# ESP-MGMT.net
KiCad netlist of a schematic drawn in Altium Designer
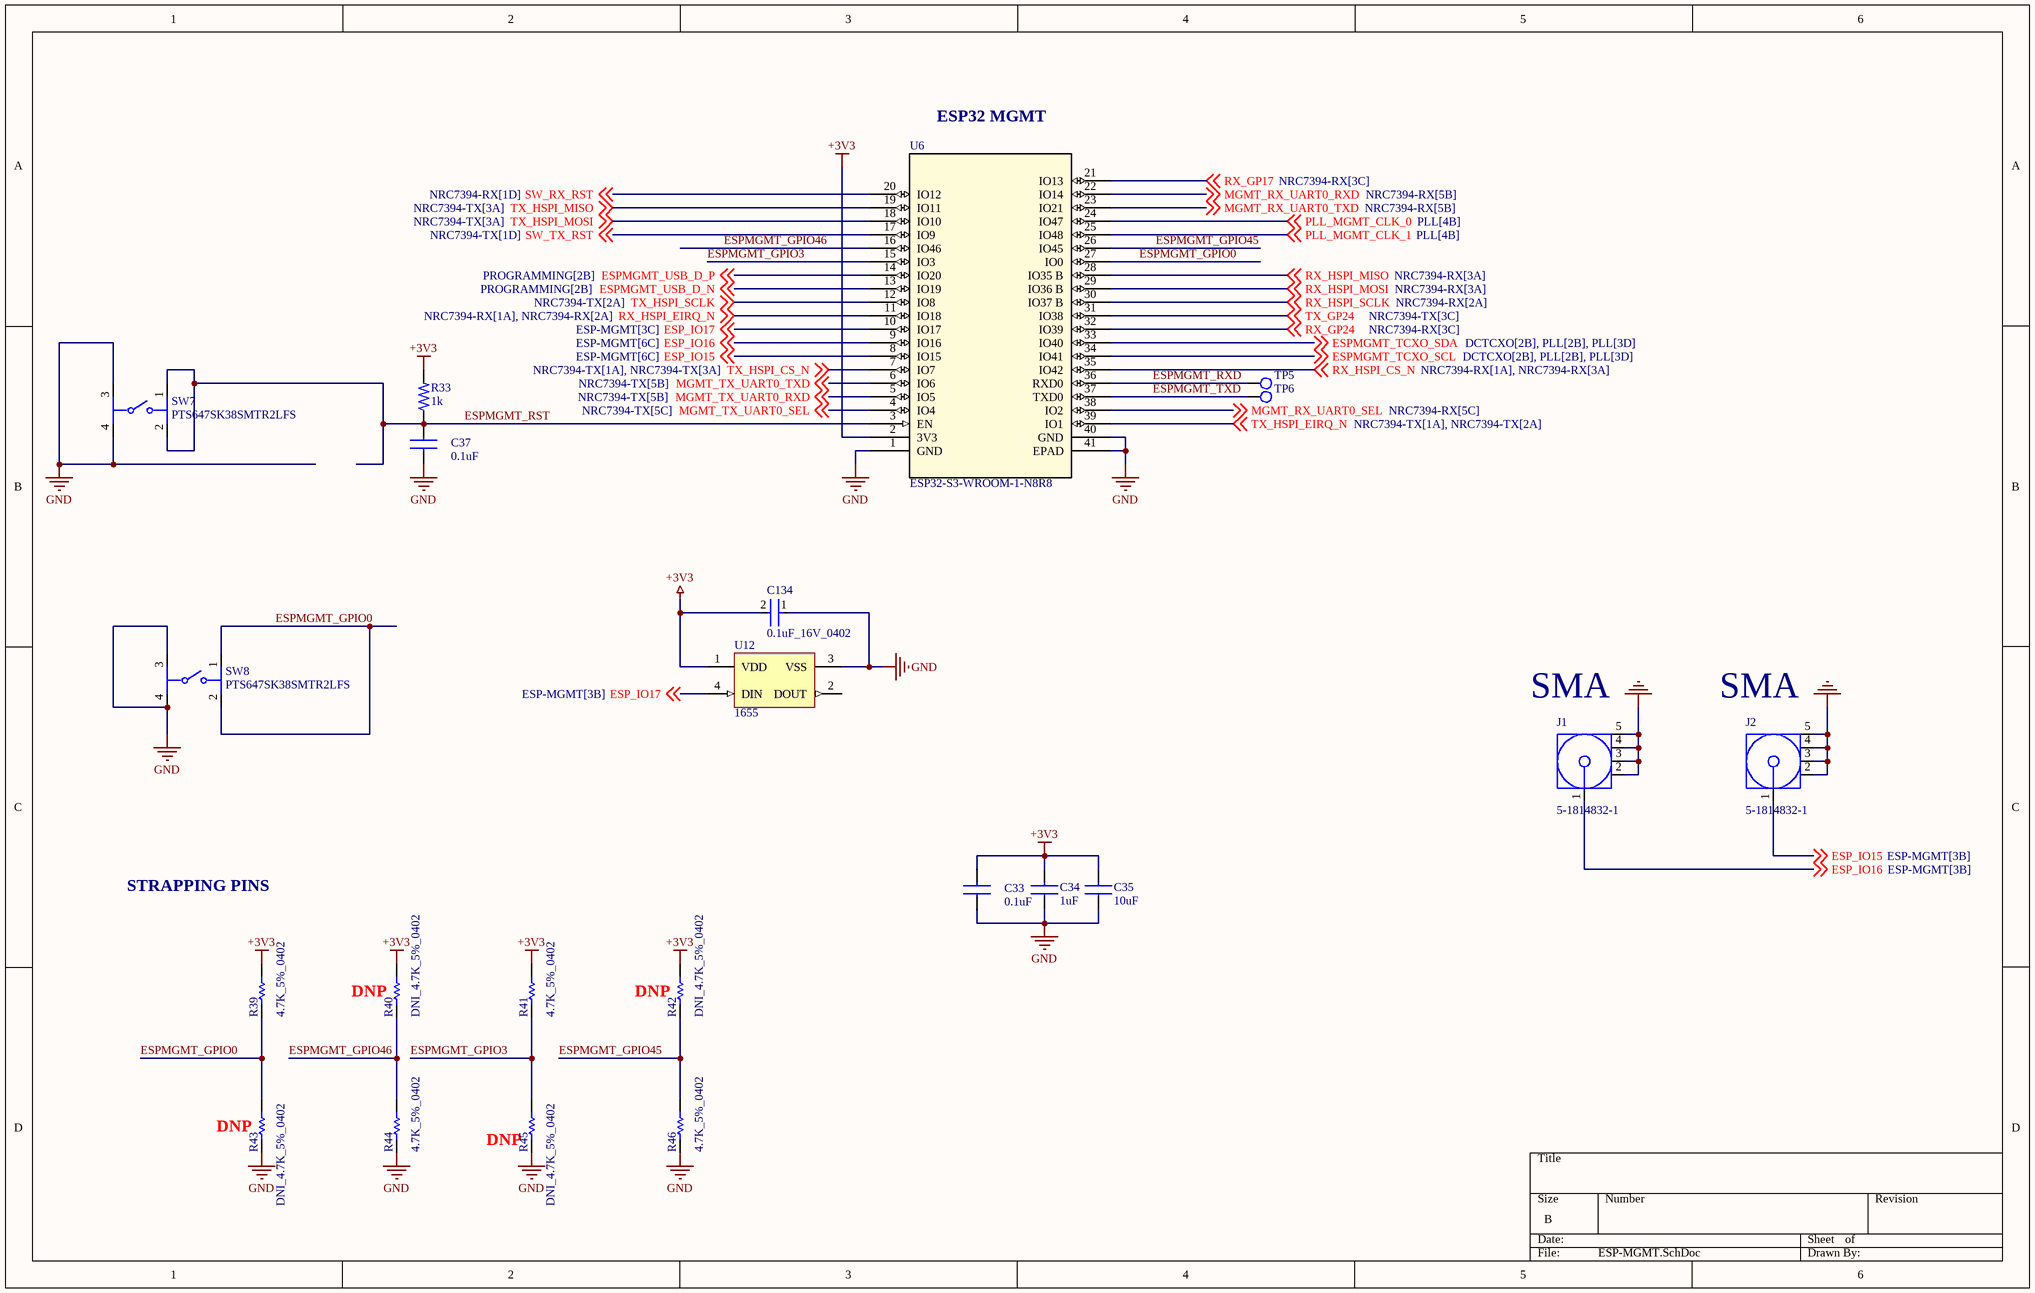
[diagram p0: ESP-MGMT.SchDoc]

(export (version "E")
  (design (tool "Eeschema 10.0.6"))
  (components
    (comp (ref "C33")
      (value "0.1uF")
      (footprint "CAP_0402")
      (description "Cap Ceramic 0.1uF 16V X7R 10% SMD 0402 125C Paper T/R")
      (fields
        (field (name "MANUFACTURER") "Murata")
        (field (name "MANUFACTURER PART NUMBER") "GCM155R71C104KA55J")
      )
      (libsource (lib "LotusSound") (part "CAP_GCM155R71C104KA55J"))
    )
    (comp (ref "C34")
      (value "1uF")
      (footprint "CAP_0402")
      (description "Cap Ceramic 1uF 25V X5R 10% SMD 0402 85°C Cardboard T/R")
      (fields
        (field (name "MANUFACTURER") "Samsung")
        (field (name "MANUFACTURER PART NUMBER") "CL05A105KA5NQNC")
      )
      (libsource (lib "LotusSound") (part "CAP_CL05A105KA5NQNC"))
    )
    (comp (ref "C35")
      (value "10uF")
      (footprint "CAP_0402")
      (description "Cap Ceramic 10uF 6.3V X5R 20% SMD 0402 85°C Paper T/R")
      (fields
        (field (name "MANUFACTURER") "Samsung")
        (field (name "MANUFACTURER PART NUMBER") "CL05A106MQ5NUNC")
      )
      (libsource (lib "LotusSound") (part "CAP_CL05A106MQ5NUNC"))
    )
    (comp (ref "C37")
      (value "0.1uF")
      (footprint "CAP_0402")
      (description "Cap Ceramic 0.1uF 16V X7R 10% SMD 0402 125C Paper T/R")
      (fields
        (field (name "MANUFACTURER") "Murata")
        (field (name "MANUFACTURER PART NUMBER") "GCM155R71C104KA55J")
      )
      (libsource (lib "LotusSound") (part "CAP_GCM155R71C104KA55J"))
    )
    (comp (ref "C134")
      (value "0.1uF_16V_0402")
      (footprint "FP-C0402-BB-MFG")
      (description "CAP CER 0.1UF 16V 20% X7R 0402")
      (fields
        (field (name "MANUFACTURER") "Kemet")
        (field (name "OCTOPART") "https://octopart.com/c0402c104m4ractu-kemet-10476575")
      )
      (libsource (lib "Altium Content Vault") (part "b4654b650e69147ec39a6b967a45e02"))
    )
    (comp (ref "J1")
      (value "5-1814832-1")
      (footprint "TECO-5-1814832-1_V")
      (fields (field (name "MANUFACTURER") "TE Connectivity"))
      (libsource (lib "Altium Content Vault") (part "CN-S-4F-RF5"))
    )
    (comp (ref "J2")
      (value "5-1814832-1")
      (footprint "TECO-5-1814832-1_V")
      (fields (field (name "MANUFACTURER") "TE Connectivity"))
      (libsource (lib "Altium Content Vault") (part "CN-S-4F-RF5"))
    )
    (comp (ref "R33")
      (value "1k")
      (footprint "RES_0402")
      (description "Res General Purpose Thick Film 0402 1K Ohm 5% 1/16W ±100ppm/°C Molded SMD Paper T/R")
      (fields
        (field (name "MANUFACTURER") "Yageo")
        (field (name "MANUFACTURER PART NUMBER") "RC0402JR-071KL")
      )
      (libsource (lib "LotusSound") (part "RES_RC0402JR-071KL"))
    )
    (comp (ref "R39")
      (value "4.7K_5%_0402")
      (footprint "RESC1005X40X25LL05T05")
      (fields (field (name "PART NUMBER") "CRCW04024K70JNTD") (field (name "MANUFACTURER") "Vishay Dale"))
      (libsource (lib "Altium Content Vault") (part "RES"))
    )
    (comp (ref "R40")
      (value "DNI_4.7K_5%_0402")
      (footprint "RESC1005X40X25LL05T05")
      (fields (field (name "PART NUMBER") "CRCW04024K70JNTD") (field (name "MANUFACTURER") "Vishay Dale"))
      (libsource (lib "Altium Content Vault") (part "RES"))
    )
    (comp (ref "R41")
      (value "4.7K_5%_0402")
      (footprint "RESC1005X40X25LL05T05")
      (fields (field (name "PART NUMBER") "CRCW04024K70JNTD") (field (name "MANUFACTURER") "Vishay Dale"))
      (libsource (lib "Altium Content Vault") (part "RES"))
    )
    (comp (ref "R42")
      (value "DNI_4.7K_5%_0402")
      (footprint "RESC1005X40X25LL05T05")
      (fields (field (name "PART NUMBER") "CRCW04024K70JNTD") (field (name "MANUFACTURER") "Vishay Dale"))
      (libsource (lib "Altium Content Vault") (part "RES"))
    )
    (comp (ref "R43")
      (value "DNI_4.7K_5%_0402")
      (footprint "RESC1005X40X25LL05T05")
      (fields (field (name "PART NUMBER") "CRCW04024K70JNTD") (field (name "MANUFACTURER") "Vishay Dale"))
      (libsource (lib "Altium Content Vault") (part "RES"))
    )
    (comp (ref "R44")
      (value "4.7K_5%_0402")
      (footprint "RESC1005X40X25LL05T05")
      (fields (field (name "PART NUMBER") "CRCW04024K70JNTD") (field (name "MANUFACTURER") "Vishay Dale"))
      (libsource (lib "Altium Content Vault") (part "RES"))
    )
    (comp (ref "R45")
      (value "DNI_4.7K_5%_0402")
      (footprint "RESC1005X40X25LL05T05")
      (fields (field (name "PART NUMBER") "CRCW04024K70JNTD") (field (name "MANUFACTURER") "Vishay Dale"))
      (libsource (lib "Altium Content Vault") (part "RES"))
    )
    (comp (ref "R46")
      (value "4.7K_5%_0402")
      (footprint "RESC1005X40X25LL05T05")
      (fields (field (name "PART NUMBER") "CRCW04024K70JNTD") (field (name "MANUFACTURER") "Vishay Dale"))
      (libsource (lib "Altium Content Vault") (part "RES"))
    )
    (comp (ref "SW7")
      (value "PTS647SK38SMTR2LFS")
      (footprint "FP-PTS647SK38SMTR2LFS-MFG")
      (description "TACT 4.5 X 4.5, 3.8 MM H, 2.5N,")
      (libsource (lib "Altium Content Vault") (part "1adf0dd01260c80cf25a44bfd6b99ba"))
    )
    (comp (ref "SW8")
      (value "PTS647SK38SMTR2LFS")
      (footprint "FP-PTS647SK38SMTR2LFS-MFG")
      (description "TACT 4.5 X 4.5, 3.8 MM H, 2.5N,")
      (libsource (lib "Altium Content Vault") (part "1adf0dd01260c80cf25a44bfd6b99ba"))
    )
    (comp (ref "TP5")
      (value "Test Point 1MM")
      (footprint "TP_PAD-1MM")
      (libsource (lib "LotusSound") (part "TP_PAD-1MM"))
    )
    (comp (ref "TP6")
      (value "Test Point 1MM")
      (footprint "TP_PAD-1MM")
      (libsource (lib "LotusSound") (part "TP_PAD-1MM"))
    )
    (comp (ref "U6")
      (value "ESP32-S3-WROOM-1-N8R8")
      (footprint "ESP32-S3-WROOM-1_EXP")
      (description "No Description Available")
      (libsource (lib "ESP32-S3-WROOM-1-N8R8") (part "ESP32-S3-WROOM-1-N8R8"))
    )
    (comp (ref "U12")
      (value "1655")
      (footprint "ADA-RGB-1655_V")
      (fields (field (name "MANUFACTURER") "Adafruit-Industries-LLC"))
      (libsource (lib "Altium Content Vault") (part "ADA-RGB-1655-4"))
    )
  )
  (nets
    (net (code "1") (name "+3V3") (class "Default")
      (node (ref "C134") (pin "2") (pinfunction "2_2") (pintype "passive"))
      (node (ref "C33") (pin "2") (pinfunction "2_2") (pintype "passive"))
      (node (ref "C34") (pin "2") (pinfunction "2_2") (pintype "passive"))
      (node (ref "C35") (pin "2") (pinfunction "2_2") (pintype "passive"))
      (node (ref "R33") (pin "2") (pinfunction "2_2") (pintype "passive"))
      (node (ref "R39") (pin "2") (pinfunction "2_2") (pintype "passive"))
      (node (ref "R40") (pin "2") (pinfunction "2_2") (pintype "passive"))
      (node (ref "R41") (pin "2") (pinfunction "2_2") (pintype "passive"))
      (node (ref "R42") (pin "2") (pinfunction "2_2") (pintype "passive"))
      (node (ref "U12") (pin "1") (pinfunction "VDD_1") (pintype "power_in"))
      (node (ref "U6") (pin "2") (pinfunction "3V3_2") (pintype "power_in"))
    )
    (net (code "2") (name "/ESPMGMT_GPIO0") (class "Default")
      (node (ref "R39") (pin "1") (pinfunction "1_1") (pintype "passive"))
      (node (ref "R43") (pin "2") (pinfunction "2_2") (pintype "passive"))
      (node (ref "SW8") (pin "1") (pinfunction "1_1") (pintype "passive"))
      (node (ref "SW8") (pin "2") (pinfunction "2_2") (pintype "passive"))
      (node (ref "U6") (pin "27") (pinfunction "IO0_27") (pintype "bidirectional"))
    )
    (net (code "3") (name "/ESPMGMT_GPIO3") (class "Default")
      (node (ref "R41") (pin "1") (pinfunction "1_1") (pintype "passive"))
      (node (ref "R45") (pin "2") (pinfunction "2_2") (pintype "passive"))
      (node (ref "U6") (pin "15") (pinfunction "IO3_15") (pintype "bidirectional"))
    )
    (net (code "4") (name "/ESPMGMT_GPIO45") (class "Default")
      (node (ref "R42") (pin "1") (pinfunction "1_1") (pintype "passive"))
      (node (ref "R46") (pin "2") (pinfunction "2_2") (pintype "passive"))
      (node (ref "U6") (pin "26") (pinfunction "IO45_26") (pintype "bidirectional"))
    )
    (net (code "5") (name "/ESPMGMT_GPIO46") (class "Default")
      (node (ref "R40") (pin "1") (pinfunction "1_1") (pintype "passive"))
      (node (ref "R44") (pin "2") (pinfunction "2_2") (pintype "passive"))
      (node (ref "U6") (pin "16") (pinfunction "IO46_16") (pintype "bidirectional"))
    )
    (net (code "6") (name "/ESPMGMT_RST") (class "Default")
      (node (ref "C37") (pin "2") (pinfunction "2_2") (pintype "passive"))
      (node (ref "R33") (pin "1") (pinfunction "1_1") (pintype "passive"))
      (node (ref "SW7") (pin "1") (pinfunction "1_1") (pintype "passive"))
      (node (ref "SW7") (pin "2") (pinfunction "2_2") (pintype "passive"))
      (node (ref "U6") (pin "3") (pinfunction "EN_3") (pintype "input"))
    )
    (net (code "7") (name "/ESPMGMT_RXD") (class "Default")
      (node (ref "TP5") (pin "1") (pinfunction "1_1") (pintype "passive"))
      (node (ref "U6") (pin "36") (pinfunction "RXD0_36") (pintype "bidirectional"))
    )
    (net (code "8") (name "/ESPMGMT_TXD") (class "Default")
      (node (ref "TP6") (pin "1") (pinfunction "1_1") (pintype "passive"))
      (node (ref "U6") (pin "37") (pinfunction "TXD0_37") (pintype "bidirectional"))
    )
    (net (code "9") (name "ESPMGMT_TCXO_SCL") (class "Default")
      (node (ref "U6") (pin "34") (pinfunction "IO41_34") (pintype "bidirectional"))
    )
    (net (code "10") (name "ESPMGMT_TCXO_SDA") (class "Default")
      (node (ref "U6") (pin "33") (pinfunction "IO40_33") (pintype "bidirectional"))
    )
    (net (code "11") (name "ESPMGMT_USB_D_N") (class "Default")
      (node (ref "U6") (pin "13") (pinfunction "IO19_13") (pintype "bidirectional"))
    )
    (net (code "12") (name "ESPMGMT_USB_D_P") (class "Default")
      (node (ref "U6") (pin "14") (pinfunction "IO20_14") (pintype "bidirectional"))
    )
    (net (code "13") (name "ESP_IO15") (class "Default")
      (node (ref "J2") (pin "1") (pinfunction "1_1") (pintype "passive"))
      (node (ref "U6") (pin "8") (pinfunction "IO15_8") (pintype "bidirectional"))
    )
    (net (code "14") (name "ESP_IO16") (class "Default")
      (node (ref "J1") (pin "1") (pinfunction "1_1") (pintype "passive"))
      (node (ref "U6") (pin "9") (pinfunction "IO16_9") (pintype "bidirectional"))
    )
    (net (code "15") (name "ESP_IO17") (class "Default")
      (node (ref "U12") (pin "4") (pinfunction "DIN_4") (pintype "input"))
      (node (ref "U6") (pin "10") (pinfunction "IO17_10") (pintype "bidirectional"))
    )
    (net (code "16") (name "GND") (class "Default")
      (node (ref "C134") (pin "1") (pinfunction "1_1") (pintype "passive"))
      (node (ref "C33") (pin "1") (pinfunction "1_1") (pintype "passive"))
      (node (ref "C34") (pin "1") (pinfunction "1_1") (pintype "passive"))
      (node (ref "C35") (pin "1") (pinfunction "1_1") (pintype "passive"))
      (node (ref "C37") (pin "1") (pinfunction "1_1") (pintype "passive"))
      (node (ref "J1") (pin "2") (pinfunction "2_2") (pintype "passive"))
      (node (ref "J1") (pin "3") (pinfunction "3_3") (pintype "passive"))
      (node (ref "J1") (pin "4") (pinfunction "4_4") (pintype "passive"))
      (node (ref "J1") (pin "5") (pinfunction "5_5") (pintype "passive"))
      (node (ref "J2") (pin "2") (pinfunction "2_2") (pintype "passive"))
      (node (ref "J2") (pin "3") (pinfunction "3_3") (pintype "passive"))
      (node (ref "J2") (pin "4") (pinfunction "4_4") (pintype "passive"))
      (node (ref "J2") (pin "5") (pinfunction "5_5") (pintype "passive"))
      (node (ref "R43") (pin "1") (pinfunction "1_1") (pintype "passive"))
      (node (ref "R44") (pin "1") (pinfunction "1_1") (pintype "passive"))
      (node (ref "R45") (pin "1") (pinfunction "1_1") (pintype "passive"))
      (node (ref "R46") (pin "1") (pinfunction "1_1") (pintype "passive"))
      (node (ref "SW7") (pin "3") (pinfunction "3_3") (pintype "passive"))
      (node (ref "SW7") (pin "4") (pinfunction "4_4") (pintype "passive"))
      (node (ref "SW8") (pin "3") (pinfunction "3_3") (pintype "passive"))
      (node (ref "SW8") (pin "4") (pinfunction "4_4") (pintype "passive"))
      (node (ref "U12") (pin "3") (pinfunction "VSS_3") (pintype "power_in"))
      (node (ref "U6") (pin "1") (pinfunction "GND_1") (pintype "power_in"))
      (node (ref "U6") (pin "40") (pinfunction "GND_40") (pintype "power_in"))
      (node (ref "U6") (pin "41") (pinfunction "EPAD_41") (pintype "power_in"))
    )
    (net (code "17") (name "MGMT_RX_UART0_RXD") (class "Default")
      (node (ref "U6") (pin "22") (pinfunction "IO14_22") (pintype "bidirectional"))
    )
    (net (code "18") (name "MGMT_RX_UART0_SEL") (class "Default")
      (node (ref "U6") (pin "38") (pinfunction "IO2_38") (pintype "bidirectional"))
    )
    (net (code "19") (name "MGMT_RX_UART0_TXD") (class "Default")
      (node (ref "U6") (pin "23") (pinfunction "IO21_23") (pintype "bidirectional"))
    )
    (net (code "20") (name "MGMT_TX_UART0_RXD") (class "Default")
      (node (ref "U6") (pin "5") (pinfunction "IO5_5") (pintype "bidirectional"))
    )
    (net (code "21") (name "MGMT_TX_UART0_SEL") (class "Default")
      (node (ref "U6") (pin "4") (pinfunction "IO4_4") (pintype "bidirectional"))
    )
    (net (code "22") (name "MGMT_TX_UART0_TXD") (class "Default")
      (node (ref "U6") (pin "6") (pinfunction "IO6_6") (pintype "bidirectional"))
    )
    (net (code "23") (name "PLL_MGMT_CLK_0") (class "Default")
      (node (ref "U6") (pin "24") (pinfunction "IO47_24") (pintype "bidirectional"))
    )
    (net (code "24") (name "PLL_MGMT_CLK_1") (class "Default")
      (node (ref "U6") (pin "25") (pinfunction "IO48_25") (pintype "bidirectional"))
    )
    (net (code "25") (name "RX_GP17") (class "Default")
      (node (ref "U6") (pin "21") (pinfunction "IO13_21") (pintype "bidirectional"))
    )
    (net (code "26") (name "RX_GP24") (class "Default")
      (node (ref "U6") (pin "32") (pinfunction "IO39_32") (pintype "bidirectional"))
    )
    (net (code "27") (name "RX_HSPI_CS_N") (class "Default")
      (node (ref "U6") (pin "35") (pinfunction "IO42_35") (pintype "bidirectional"))
    )
    (net (code "28") (name "RX_HSPI_EIRQ_N") (class "Default")
      (node (ref "U6") (pin "11") (pinfunction "IO18_11") (pintype "bidirectional"))
    )
    (net (code "29") (name "RX_HSPI_MISO") (class "Default")
      (node (ref "U6") (pin "28") (pinfunction "IO35_B_28") (pintype "bidirectional"))
    )
    (net (code "30") (name "RX_HSPI_MOSI") (class "Default")
      (node (ref "U6") (pin "29") (pinfunction "IO36_B_29") (pintype "bidirectional"))
    )
    (net (code "31") (name "RX_HSPI_SCLK") (class "Default")
      (node (ref "U6") (pin "30") (pinfunction "IO37_B_30") (pintype "bidirectional"))
    )
    (net (code "32") (name "SW_RX_RST") (class "Default")
      (node (ref "U6") (pin "20") (pinfunction "IO12_20") (pintype "bidirectional"))
    )
    (net (code "33") (name "SW_TX_RST") (class "Default")
      (node (ref "U6") (pin "17") (pinfunction "IO9_17") (pintype "bidirectional"))
    )
    (net (code "34") (name "TX_GP24") (class "Default")
      (node (ref "U6") (pin "31") (pinfunction "IO38_31") (pintype "bidirectional"))
    )
    (net (code "35") (name "TX_HSPI_CS_N") (class "Default")
      (node (ref "U6") (pin "7") (pinfunction "IO7_7") (pintype "bidirectional"))
    )
    (net (code "36") (name "TX_HSPI_EIRQ_N") (class "Default")
      (node (ref "U6") (pin "39") (pinfunction "IO1_39") (pintype "bidirectional"))
    )
    (net (code "37") (name "TX_HSPI_MISO") (class "Default")
      (node (ref "U6") (pin "19") (pinfunction "IO11_19") (pintype "bidirectional"))
    )
    (net (code "38") (name "TX_HSPI_MOSI") (class "Default")
      (node (ref "U6") (pin "18") (pinfunction "IO10_18") (pintype "bidirectional"))
    )
    (net (code "39") (name "TX_HSPI_SCLK") (class "Default")
      (node (ref "U6") (pin "12") (pinfunction "IO8_12") (pintype "bidirectional"))
    )
    (net (code "40") (name "unconnected-(U12-DOUT-Pad2)") (class "Default")
      (node (ref "U12") (pin "2") (pinfunction "DOUT_2") (pintype "output"))
    )
  )
)
